# 01-Breadboard.net
KiCad netlist of a schematic drawn in Altium Designer
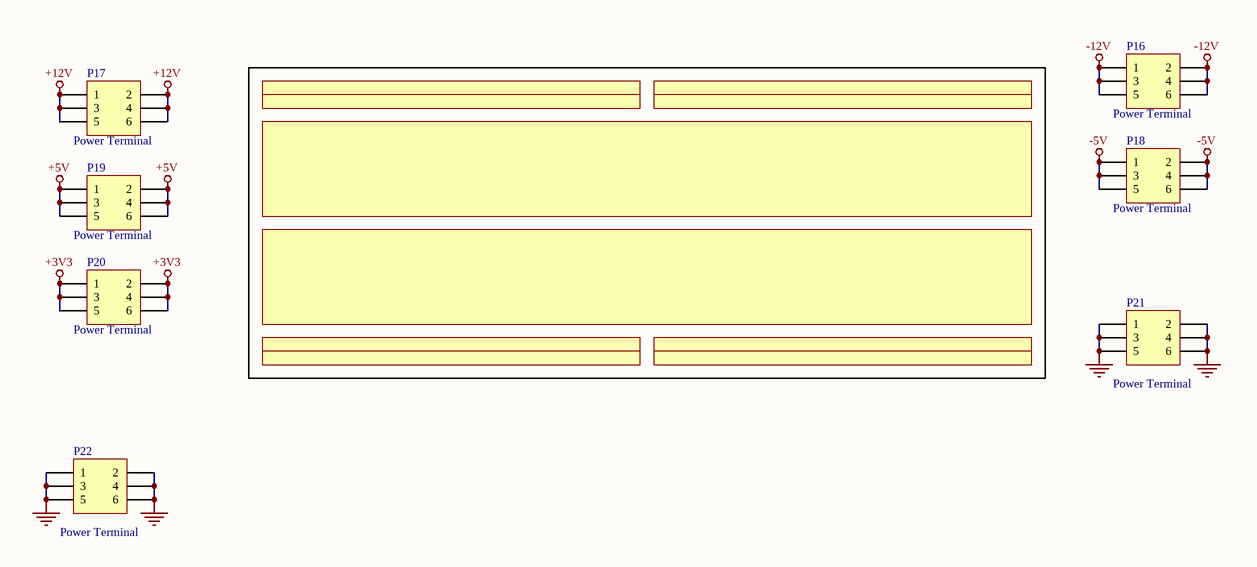
[diagram p0: 01-Breadboard.SchDoc]

(export (version "E")
  (design (tool "Eeschema 10.0.6"))
  (components
    (comp (ref "P16")
      (value "Power Terminal")
      (footprint "HDR2X3")
      (description "Header, 3-Pin, Dual row")
      (fields (field (name "Comment") "Header 3X2"))
      (libsource (lib "Miscellaneous Connectors") (part "Header 3X2"))
    )
    (comp (ref "P17")
      (value "Power Terminal")
      (footprint "HDR2X3")
      (description "Header, 3-Pin, Dual row")
      (fields (field (name "Comment") "Header 3X2"))
      (libsource (lib "Miscellaneous Connectors") (part "Header 3X2"))
    )
    (comp (ref "P18")
      (value "Power Terminal")
      (footprint "HDR2X3")
      (description "Header, 3-Pin, Dual row")
      (fields (field (name "Comment") "Header 3X2"))
      (libsource (lib "Miscellaneous Connectors") (part "Header 3X2"))
    )
    (comp (ref "P19")
      (value "Power Terminal")
      (footprint "HDR2X3")
      (description "Header, 3-Pin, Dual row")
      (fields (field (name "Comment") "Header 3X2"))
      (libsource (lib "Miscellaneous Connectors") (part "Header 3X2"))
    )
    (comp (ref "P20")
      (value "Power Terminal")
      (footprint "HDR2X3")
      (description "Header, 3-Pin, Dual row")
      (fields (field (name "Comment") "Header 3X2"))
      (libsource (lib "Miscellaneous Connectors") (part "Header 3X2"))
    )
    (comp (ref "P21")
      (value "Power Terminal")
      (footprint "HDR2X3")
      (description "Header, 3-Pin, Dual row")
      (fields (field (name "Comment") "Header 3X2"))
      (libsource (lib "Miscellaneous Connectors") (part "Header 3X2"))
    )
    (comp (ref "P22")
      (value "Power Terminal")
      (footprint "HDR2X3")
      (description "Header, 3-Pin, Dual row")
      (fields (field (name "Comment") "Header 3X2"))
      (libsource (lib "Miscellaneous Connectors") (part "Header 3X2"))
    )
  )
  (nets
    (net (code "1") (name "+3V3") (class "Default")
      (node (ref "P20") (pin "1") (pinfunction "1_1") (pintype "passive"))
      (node (ref "P20") (pin "2") (pinfunction "2_2") (pintype "passive"))
      (node (ref "P20") (pin "3") (pinfunction "3_3") (pintype "passive"))
      (node (ref "P20") (pin "4") (pinfunction "4_4") (pintype "passive"))
      (node (ref "P20") (pin "5") (pinfunction "5_5") (pintype "passive"))
      (node (ref "P20") (pin "6") (pinfunction "6_6") (pintype "passive"))
    )
    (net (code "2") (name "+5V") (class "Default")
      (node (ref "P19") (pin "1") (pinfunction "1_1") (pintype "passive"))
      (node (ref "P19") (pin "2") (pinfunction "2_2") (pintype "passive"))
      (node (ref "P19") (pin "3") (pinfunction "3_3") (pintype "passive"))
      (node (ref "P19") (pin "4") (pinfunction "4_4") (pintype "passive"))
      (node (ref "P19") (pin "5") (pinfunction "5_5") (pintype "passive"))
      (node (ref "P19") (pin "6") (pinfunction "6_6") (pintype "passive"))
    )
    (net (code "3") (name "+12V") (class "Default")
      (node (ref "P17") (pin "1") (pinfunction "1_1") (pintype "passive"))
      (node (ref "P17") (pin "2") (pinfunction "2_2") (pintype "passive"))
      (node (ref "P17") (pin "3") (pinfunction "3_3") (pintype "passive"))
      (node (ref "P17") (pin "4") (pinfunction "4_4") (pintype "passive"))
      (node (ref "P17") (pin "5") (pinfunction "5_5") (pintype "passive"))
      (node (ref "P17") (pin "6") (pinfunction "6_6") (pintype "passive"))
    )
    (net (code "4") (name "-5V") (class "Default")
      (node (ref "P18") (pin "1") (pinfunction "1_1") (pintype "passive"))
      (node (ref "P18") (pin "2") (pinfunction "2_2") (pintype "passive"))
      (node (ref "P18") (pin "3") (pinfunction "3_3") (pintype "passive"))
      (node (ref "P18") (pin "4") (pinfunction "4_4") (pintype "passive"))
      (node (ref "P18") (pin "5") (pinfunction "5_5") (pintype "passive"))
      (node (ref "P18") (pin "6") (pinfunction "6_6") (pintype "passive"))
    )
    (net (code "5") (name "-12V") (class "Default")
      (node (ref "P16") (pin "1") (pinfunction "1_1") (pintype "passive"))
      (node (ref "P16") (pin "2") (pinfunction "2_2") (pintype "passive"))
      (node (ref "P16") (pin "3") (pinfunction "3_3") (pintype "passive"))
      (node (ref "P16") (pin "4") (pinfunction "4_4") (pintype "passive"))
      (node (ref "P16") (pin "5") (pinfunction "5_5") (pintype "passive"))
      (node (ref "P16") (pin "6") (pinfunction "6_6") (pintype "passive"))
    )
    (net (code "6") (name "GND") (class "Default")
      (node (ref "P21") (pin "1") (pinfunction "1_1") (pintype "passive"))
      (node (ref "P21") (pin "2") (pinfunction "2_2") (pintype "passive"))
      (node (ref "P21") (pin "3") (pinfunction "3_3") (pintype "passive"))
      (node (ref "P21") (pin "4") (pinfunction "4_4") (pintype "passive"))
      (node (ref "P21") (pin "5") (pinfunction "5_5") (pintype "passive"))
      (node (ref "P21") (pin "6") (pinfunction "6_6") (pintype "passive"))
      (node (ref "P22") (pin "1") (pinfunction "1_1") (pintype "passive"))
      (node (ref "P22") (pin "2") (pinfunction "2_2") (pintype "passive"))
      (node (ref "P22") (pin "3") (pinfunction "3_3") (pintype "passive"))
      (node (ref "P22") (pin "4") (pinfunction "4_4") (pintype "passive"))
      (node (ref "P22") (pin "5") (pinfunction "5_5") (pintype "passive"))
      (node (ref "P22") (pin "6") (pinfunction "6_6") (pintype "passive"))
    )
  )
)
